# TSE_mother_board_periph_commutation.net
KiCad netlist of a schematic drawn in Altium Designer
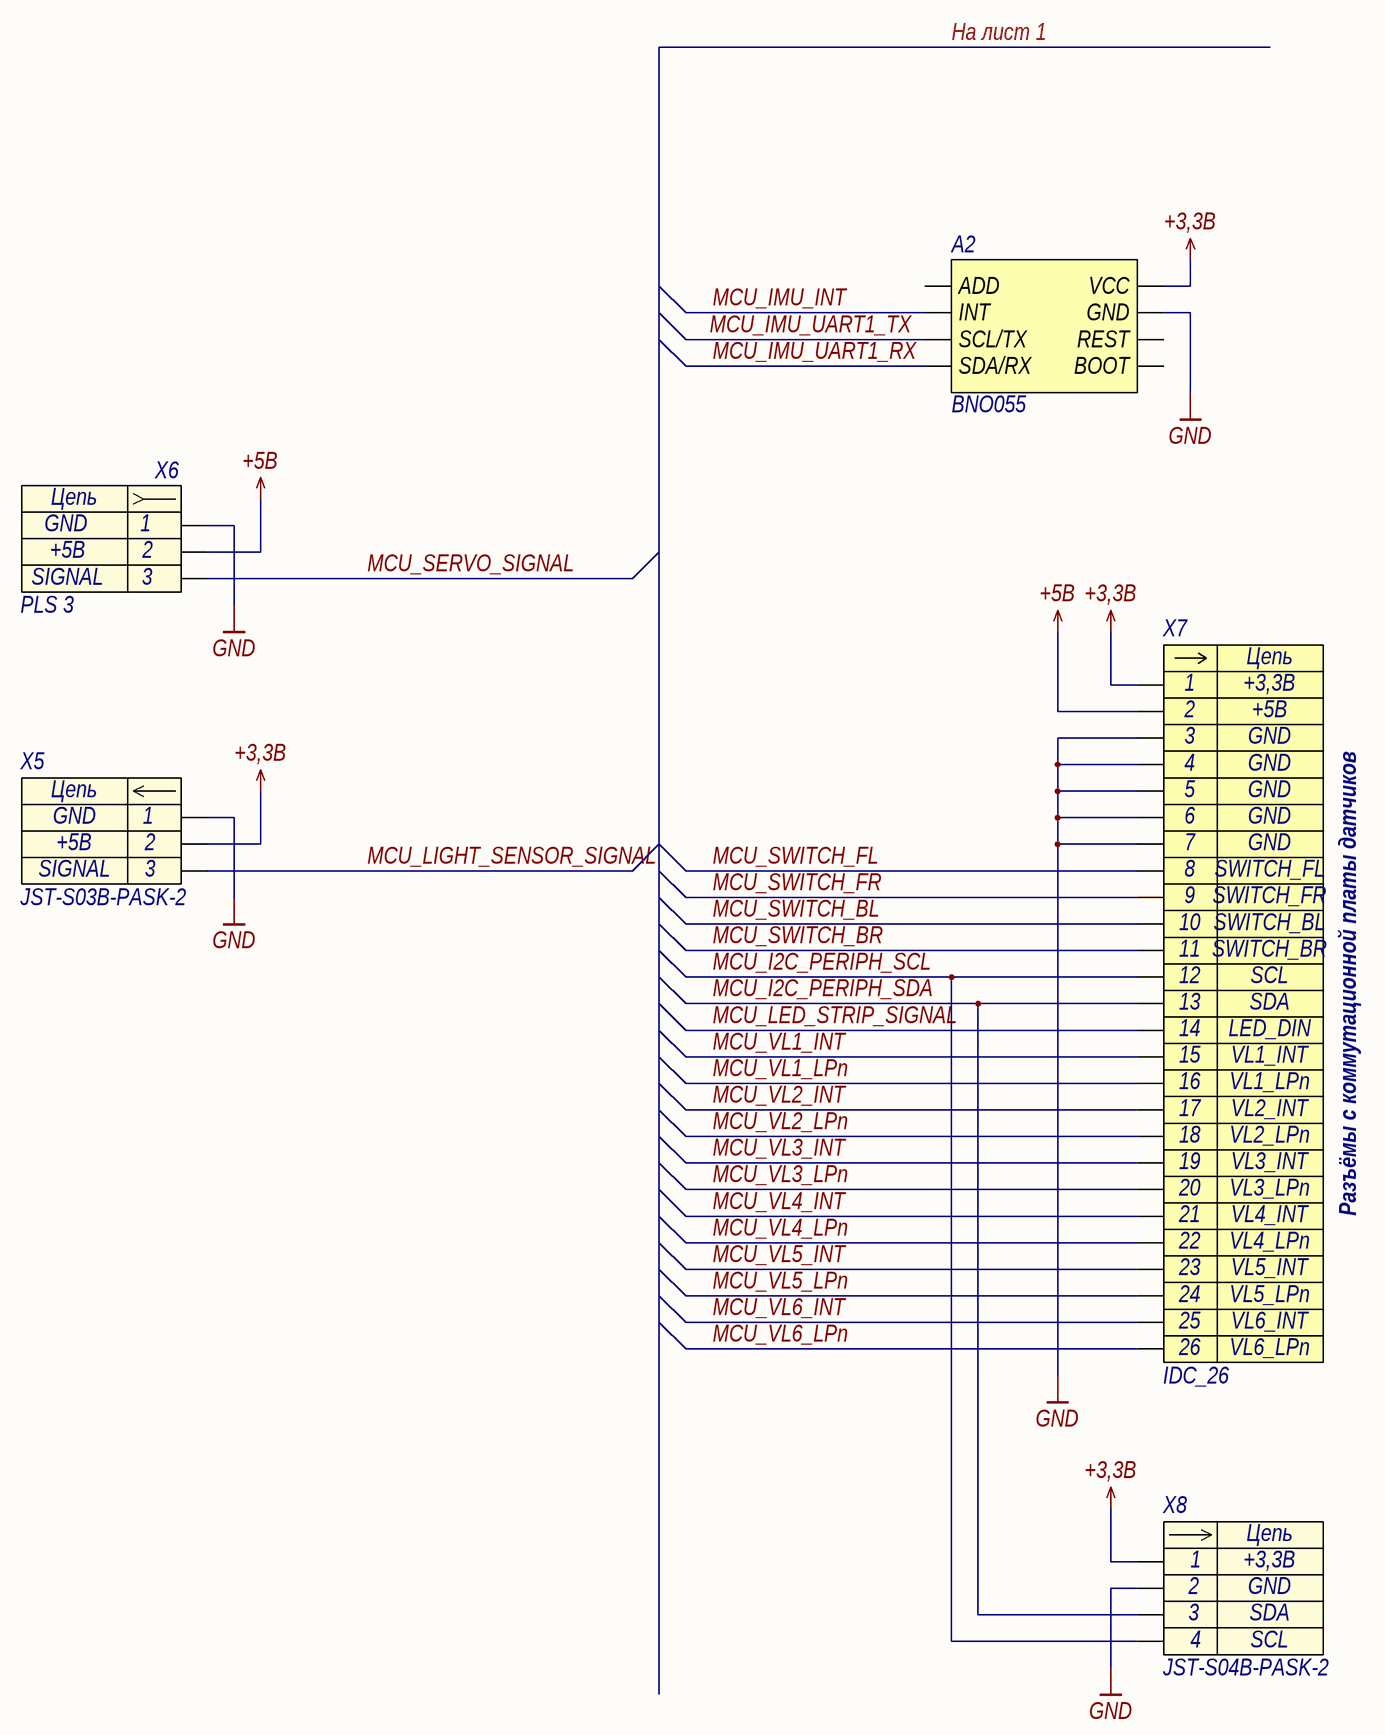
[diagram p0: TSE_mother_board_periph_commutation.SchDoc]

(export (version "E")
  (design (tool "Eeschema 10.0.6"))
  (components
    (comp (ref "A2")
      (value "BNO055")
      (footprint "BNO055")
      (description "9-осевой гироскоп и акселерометр")
      (libsource (lib "ics") (part "BNO055"))
    )
    (comp (ref "X5")
      (value "JST-S03B-PASK-2")
      (footprint "JST-S03B-PASK-2")
      (description "Разъем - 3 конт. угловая вилка на плату, шаг 2,00 мм")
      (libsource (lib "headers") (part "JST-S03B-PASK-2"))
    )
    (comp (ref "X6")
      (value "PLS 3")
      (footprint "pls-2,54-3-tht-v")
      (description "Разъем - 6 конт. 3, шаг 2,54 мм")
      (libsource (lib "headers") (part "PLS-3 ICSP_1"))
    )
    (comp (ref "X7")
      (value "IDC_26")
      (footprint "IDC1.27_26")
      (description "Разъем - 26 конт. прямая вилка на плату")
      (libsource (lib "headers") (part "IDC_26"))
    )
    (comp (ref "X8")
      (value "JST-S04B-PASK-2")
      (footprint "JST-S04B-PASK-2")
      (description "Разъем - 4 конт. угловая вилка на плату, шаг 2,00 мм")
      (libsource (lib "headers") (part "JST-S04B-PASK-2"))
    )
  )
  (nets
    (net (code "1") (name "+3,3В") (class "Default")
      (node (ref "A2") (pin "1") (pinfunction "VCC_1") (pintype "passive"))
      (node (ref "X5") (pin "2") (pinfunction "2_2") (pintype "passive"))
      (node (ref "X7") (pin "1") (pinfunction "1_1") (pintype "passive"))
      (node (ref "X8") (pin "1") (pinfunction "1_1") (pintype "passive"))
    )
    (net (code "2") (name "+5В") (class "Default")
      (node (ref "X6") (pin "2") (pinfunction "2_2") (pintype "passive"))
      (node (ref "X7") (pin "2") (pinfunction "2_2") (pintype "passive"))
    )
    (net (code "3") (name "/MCU_I2C_PERIPH_SCL") (class "Default")
      (node (ref "X7") (pin "12") (pinfunction "12_12") (pintype "passive"))
      (node (ref "X8") (pin "4") (pinfunction "4_4") (pintype "passive"))
    )
    (net (code "4") (name "/MCU_I2C_PERIPH_SDA") (class "Default")
      (node (ref "X7") (pin "13") (pinfunction "13_13") (pintype "passive"))
      (node (ref "X8") (pin "3") (pinfunction "3_3") (pintype "passive"))
    )
    (net (code "5") (name "/MCU_IMU_INT") (class "Default")
      (node (ref "A2") (pin "6") (pinfunction "INT_6") (pintype "passive"))
    )
    (net (code "6") (name "/MCU_IMU_UART1_RX") (class "Default")
      (node (ref "A2") (pin "3") (pinfunction "SDA/RX_3") (pintype "passive"))
    )
    (net (code "7") (name "/MCU_IMU_UART1_TX") (class "Default")
      (node (ref "A2") (pin "4") (pinfunction "SCL/TX_4") (pintype "passive"))
    )
    (net (code "8") (name "/MCU_LED_STRIP_SIGNAL") (class "Default")
      (node (ref "X7") (pin "14") (pinfunction "14_14") (pintype "passive"))
    )
    (net (code "9") (name "/MCU_LIGHT_SENSOR_SIGNAL") (class "Default")
      (node (ref "X5") (pin "3") (pinfunction "3_3") (pintype "passive"))
    )
    (net (code "10") (name "/MCU_SERVO_SIGNAL") (class "Default")
      (node (ref "X6") (pin "3") (pinfunction "3_3") (pintype "passive"))
    )
    (net (code "11") (name "/MCU_SWITCH_BL") (class "Default")
      (node (ref "X7") (pin "10") (pinfunction "10_10") (pintype "passive"))
    )
    (net (code "12") (name "/MCU_SWITCH_BR") (class "Default")
      (node (ref "X7") (pin "11") (pinfunction "11_11") (pintype "passive"))
    )
    (net (code "13") (name "/MCU_SWITCH_FL") (class "Default")
      (node (ref "X7") (pin "8") (pinfunction "8_8") (pintype "passive"))
    )
    (net (code "14") (name "/MCU_SWITCH_FR") (class "Default")
      (node (ref "X7") (pin "9") (pinfunction "9_9") (pintype "passive"))
    )
    (net (code "15") (name "/MCU_VL1_INT") (class "Default")
      (node (ref "X7") (pin "15") (pinfunction "15_15") (pintype "passive"))
    )
    (net (code "16") (name "/MCU_VL1_LPn") (class "Default")
      (node (ref "X7") (pin "16") (pinfunction "16_16") (pintype "passive"))
    )
    (net (code "17") (name "/MCU_VL2_INT") (class "Default")
      (node (ref "X7") (pin "17") (pinfunction "17_17") (pintype "passive"))
    )
    (net (code "18") (name "/MCU_VL2_LPn") (class "Default")
      (node (ref "X7") (pin "18") (pinfunction "18_18") (pintype "passive"))
    )
    (net (code "19") (name "/MCU_VL3_INT") (class "Default")
      (node (ref "X7") (pin "19") (pinfunction "19_19") (pintype "passive"))
    )
    (net (code "20") (name "/MCU_VL3_LPn") (class "Default")
      (node (ref "X7") (pin "20") (pinfunction "20_20") (pintype "passive"))
    )
    (net (code "21") (name "/MCU_VL4_INT") (class "Default")
      (node (ref "X7") (pin "21") (pinfunction "21_21") (pintype "passive"))
    )
    (net (code "22") (name "/MCU_VL4_LPn") (class "Default")
      (node (ref "X7") (pin "22") (pinfunction "22_22") (pintype "passive"))
    )
    (net (code "23") (name "/MCU_VL5_INT") (class "Default")
      (node (ref "X7") (pin "23") (pinfunction "23_23") (pintype "passive"))
    )
    (net (code "24") (name "/MCU_VL5_LPn") (class "Default")
      (node (ref "X7") (pin "24") (pinfunction "24_24") (pintype "passive"))
    )
    (net (code "25") (name "/MCU_VL6_INT") (class "Default")
      (node (ref "X7") (pin "25") (pinfunction "25_25") (pintype "passive"))
    )
    (net (code "26") (name "/MCU_VL6_LPn") (class "Default")
      (node (ref "X7") (pin "26") (pinfunction "26_26") (pintype "passive"))
    )
    (net (code "27") (name "GND") (class "Default")
      (node (ref "A2") (pin "2") (pinfunction "GND_2") (pintype "passive"))
      (node (ref "X5") (pin "1") (pinfunction "1_1") (pintype "passive"))
      (node (ref "X6") (pin "1") (pinfunction "1_1") (pintype "passive"))
      (node (ref "X7") (pin "3") (pinfunction "3_3") (pintype "passive"))
      (node (ref "X7") (pin "4") (pinfunction "4_4") (pintype "passive"))
      (node (ref "X7") (pin "5") (pinfunction "5_5") (pintype "passive"))
      (node (ref "X7") (pin "6") (pinfunction "6_6") (pintype "passive"))
      (node (ref "X7") (pin "7") (pinfunction "7_7") (pintype "passive"))
      (node (ref "X8") (pin "2") (pinfunction "2_2") (pintype "passive"))
    )
    (net (code "28") (name "unconnected-(A2-ADD-Pad5)") (class "Default")
      (node (ref "A2") (pin "5") (pinfunction "ADD_5") (pintype "passive"))
    )
    (net (code "29") (name "unconnected-(A2-BOOT-Pad7)") (class "Default")
      (node (ref "A2") (pin "7") (pinfunction "BOOT_7") (pintype "passive"))
    )
    (net (code "30") (name "unconnected-(A2-REST-Pad8)") (class "Default")
      (node (ref "A2") (pin "8") (pinfunction "REST_8") (pintype "passive"))
    )
  )
)
